# Connector.net
KiCad netlist of a schematic drawn in Altium Designer
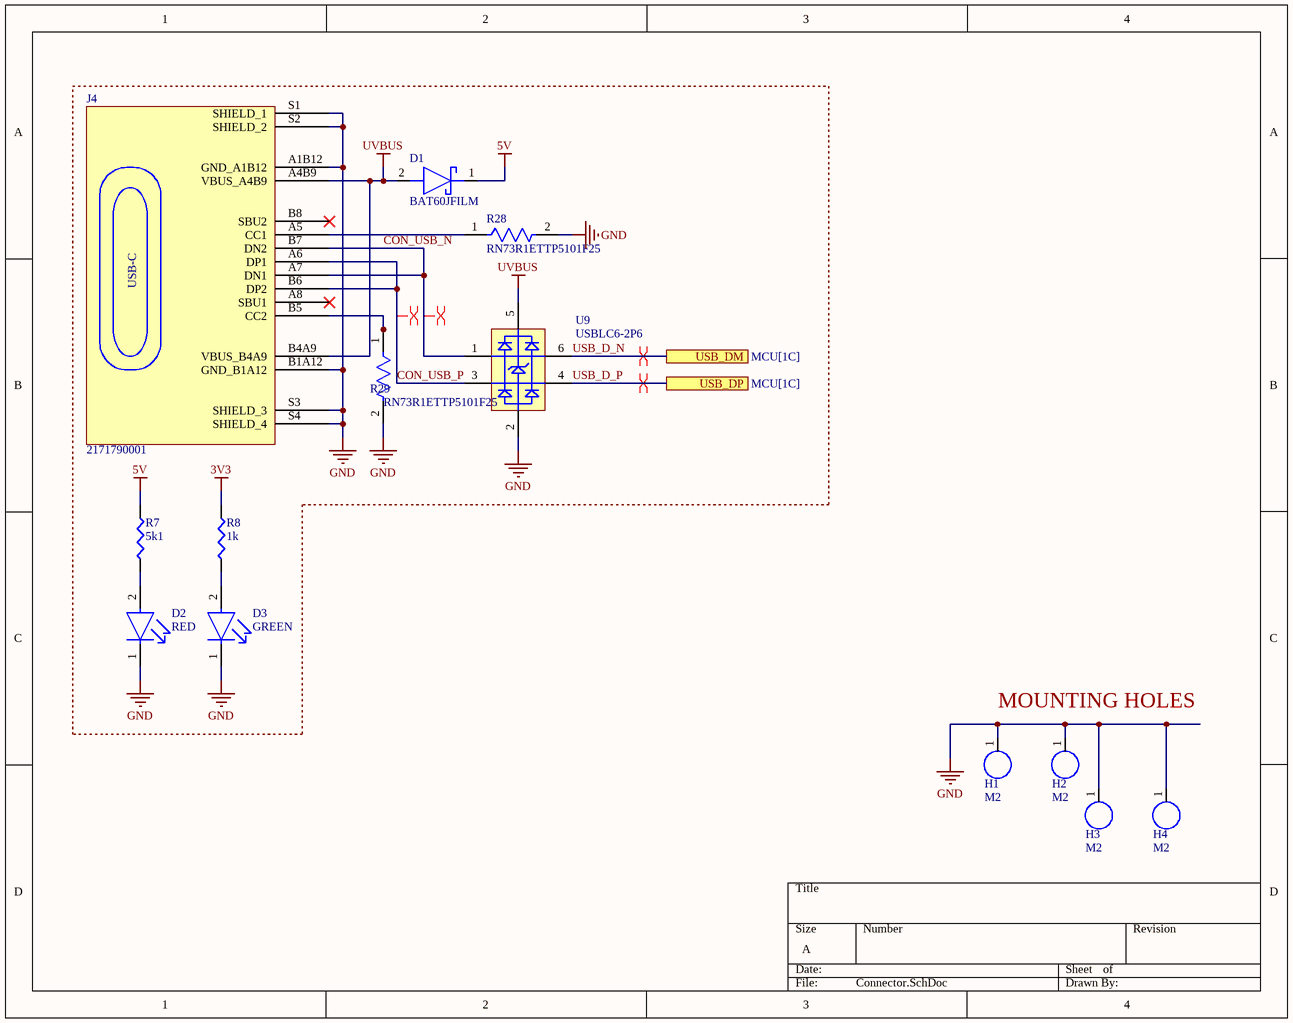
[diagram p0: Connector.SchDoc]

(export (version "E")
  (design (tool "Eeschema 10.0.6"))
  (components
    (comp (ref "D1")
      (value "BAT60JFILM")
      (footprint "SOD2513X117N")
      (description "Diode Small Signal Schottky 10V 3A Automotive 2-Pin SOD-323 T/R")
      (fields (field (name "MANUFACTURER") "STMicroelectronics") (field (name "LCSC PART #") "C133103"))
      (libsource (lib "Flight_Computer1") (part "D_Schotty_Diode"))
    )
    (comp (ref "D2")
      (value "RED")
      (footprint "LEDC1005X35N")
      (description "RED LED")
      (fields (field (name "LCSC PART #") "C397045"))
      (libsource (lib "Flight_Computer1") (part "D_RED_LED"))
    )
    (comp (ref "D3")
      (value "GREEN")
      (footprint "LEDC1005X35N")
      (description "Green LED")
      (fields (field (name "LCSC PART #") "C434446"))
      (libsource (lib "Flight_Computer1") (part "D_GREEN_LED"))
    )
    (comp (ref "H1")
      (value "M2")
      (footprint "Mounting Hole")
      (description "2mm M2 Mounting Hole")
      (libsource (lib "Schlib1") (part "M2 Mounting Hole"))
    )
    (comp (ref "H2")
      (value "M2")
      (footprint "Mounting Hole")
      (description "2mm M2 Mounting Hole")
      (libsource (lib "Schlib1") (part "M2 Mounting Hole"))
    )
    (comp (ref "H3")
      (value "M2")
      (footprint "Mounting Hole")
      (description "2mm M2 Mounting Hole")
      (libsource (lib "Schlib1") (part "M2 Mounting Hole"))
    )
    (comp (ref "H4")
      (value "M2")
      (footprint "Mounting Hole")
      (description "2mm M2 Mounting Hole")
      (libsource (lib "Schlib1") (part "M2 Mounting Hole"))
    )
    (comp (ref "J4")
      (value "2171790001")
      (footprint "FP-2171790001-MFG")
      (description "CONN RCP USB2.0 TYP C 24P SMD RA")
      (fields (field (name "MANUFACTURER") "Molex") (field (name "MANUFACTURER PART NUMBER") "217179-0001"))
      (libsource (lib "Flight_Computer1") (part "217179-0001"))
    )
    (comp (ref "R7")
      (value "5k1")
      (footprint "0402_R")
      (description "Res Thick Film 0402 5.1K Ohm 1% 0.063W(1/16W) ±100ppm/C Pad SMD T/R")
      (fields
        (field (name "MANUFACTURER") "Yageo Group")
        (field (name "MANUFACTURER PART NUMBER") "RC0402FR-135K1L")
      )
      (libsource (lib "Flight_Computer1") (part "R_5K1_0402"))
    )
    (comp (ref "R8")
      (value "1k")
      (footprint "0402_R")
      (description "RES 1K OHM 1% 1/16W 0402")
      (fields (field (name "LCSC PART #") "C106235") (field (name "MANUFACTURER") "Yageo Group"))
      (libsource (lib "Flight_Computer1") (part "R_1k_0402"))
    )
    (comp (ref "R28")
      (value "RN73R1ETTP5101F25")
      (footprint "FP-RN73R1E-IPC_C")
      (description "5.1kΩ ±1% 0.063W, 1/16W Chip Resistor 0402 (1005 Metric) Moisture Resistant Thin Film")
      (libsource (lib "Altium Content Vault") (part "1029c3af85768c4190bb7ad29bc67b5"))
    )
    (comp (ref "R29")
      (value "RN73R1ETTP5101F25")
      (footprint "FP-RN73R1E-IPC_C")
      (description "5.1kΩ ±1% 0.063W, 1/16W Chip Resistor 0402 (1005 Metric) Moisture Resistant Thin Film")
      (libsource (lib "Altium Content Vault") (part "1029c3af85768c4190bb7ad29bc67b5"))
    )
    (comp (ref "U9")
      (value "USBLC6-2P6")
      (footprint "USBLC62P6")
      (description "Integrated Circuit")
      (fields (field (name "MOUSER PART NUMBER") "511-USBLC6-2P6") (field (name "LCSC PART #") "C15999"))
      (libsource (lib "Flight_Computer1") (part "USBLC6-2P6"))
    )
  )
  (nets
    (net (code "1") (name "/CON_USB_N") (class "Default")
      (node (ref "J4") (pin "A7") (pinfunction "DN1_A7") (pintype "passive"))
      (node (ref "J4") (pin "B7") (pinfunction "DN2_B7") (pintype "passive"))
      (node (ref "U9") (pin "1") (pinfunction "I/O1_1_1") (pintype "passive"))
    )
    (net (code "2") (name "/CON_USB_P") (class "Default")
      (node (ref "J4") (pin "A6") (pinfunction "DP1_A6") (pintype "passive"))
      (node (ref "J4") (pin "B6") (pinfunction "DP2_B6") (pintype "passive"))
      (node (ref "U9") (pin "3") (pinfunction "I/O2_1_3") (pintype "passive"))
    )
    (net (code "3") (name "/USB_D_N") (class "Default")
      (node (ref "U9") (pin "6") (pinfunction "I/O1_2_6") (pintype "passive"))
    )
    (net (code "4") (name "/USB_D_P") (class "Default")
      (node (ref "U9") (pin "4") (pinfunction "I/O2_2_4") (pintype "passive"))
    )
    (net (code "5") (name "3V3") (class "Default")
      (node (ref "R8") (pin "2") (pinfunction "2_2") (pintype "passive"))
    )
    (net (code "6") (name "5V") (class "Default")
      (node (ref "D1") (pin "1") (pinfunction "K_1") (pintype "passive"))
      (node (ref "R7") (pin "2") (pinfunction "2_2") (pintype "passive"))
    )
    (net (code "7") (name "GND") (class "Default")
      (node (ref "D2") (pin "1") (pinfunction "C_1") (pintype "passive"))
      (node (ref "D3") (pin "1") (pinfunction "C_1") (pintype "passive"))
      (node (ref "H1") (pin "1") (pinfunction "1_1") (pintype "passive"))
      (node (ref "H2") (pin "1") (pinfunction "1_1") (pintype "passive"))
      (node (ref "H3") (pin "1") (pinfunction "1_1") (pintype "passive"))
      (node (ref "H4") (pin "1") (pinfunction "1_1") (pintype "passive"))
      (node (ref "J4") (pin "A1B12") (pinfunction "GND_A1B12_A1B12") (pintype "passive"))
      (node (ref "J4") (pin "B1A12") (pinfunction "GND_B1A12_B1A12") (pintype "passive"))
      (node (ref "J4") (pin "S1") (pinfunction "SHIELD_1_S1") (pintype "passive"))
      (node (ref "J4") (pin "S2") (pinfunction "SHIELD_2_S2") (pintype "passive"))
      (node (ref "J4") (pin "S3") (pinfunction "SHIELD_3_S3") (pintype "passive"))
      (node (ref "J4") (pin "S4") (pinfunction "SHIELD_4_S4") (pintype "passive"))
      (node (ref "R28") (pin "2") (pinfunction "2_2") (pintype "passive"))
      (node (ref "R29") (pin "2") (pinfunction "2_2") (pintype "passive"))
      (node (ref "U9") (pin "2") (pinfunction "GND_2") (pintype "passive"))
    )
    (net (code "8") (name "Net-(D2-A)") (class "Default")
      (node (ref "D2") (pin "2") (pinfunction "A_2") (pintype "passive"))
      (node (ref "R7") (pin "1") (pinfunction "1_1") (pintype "passive"))
    )
    (net (code "9") (name "Net-(D3-A)") (class "Default")
      (node (ref "D3") (pin "2") (pinfunction "A_2") (pintype "passive"))
      (node (ref "R8") (pin "1") (pinfunction "1_1") (pintype "passive"))
    )
    (net (code "10") (name "Net-(J4-CC1)") (class "Default")
      (node (ref "J4") (pin "A5") (pinfunction "CC1_A5") (pintype "passive"))
      (node (ref "R28") (pin "1") (pinfunction "1_1") (pintype "passive"))
    )
    (net (code "11") (name "Net-(J4-CC2)") (class "Default")
      (node (ref "J4") (pin "B5") (pinfunction "CC2_B5") (pintype "passive"))
      (node (ref "R29") (pin "1") (pinfunction "1_1") (pintype "passive"))
    )
    (net (code "12") (name "UVBUS") (class "Default")
      (node (ref "D1") (pin "2") (pinfunction "A_2") (pintype "passive"))
      (node (ref "J4") (pin "A4B9") (pinfunction "VBUS_A4B9_A4B9") (pintype "passive"))
      (node (ref "J4") (pin "B4A9") (pinfunction "VBUS_B4A9_B4A9") (pintype "passive"))
      (node (ref "U9") (pin "5") (pinfunction "VBUS_5") (pintype "passive"))
    )
    (net (code "13") (name "unconnected-(J4-SBU1-PadA8)") (class "Default")
      (node (ref "J4") (pin "A8") (pinfunction "SBU1_A8") (pintype "passive+no_connect"))
    )
    (net (code "14") (name "unconnected-(J4-SBU2-PadB8)") (class "Default")
      (node (ref "J4") (pin "B8") (pinfunction "SBU2_B8") (pintype "passive+no_connect"))
    )
  )
)
